# Sheet1.net
KiCad netlist of a schematic drawn in Altium Designer
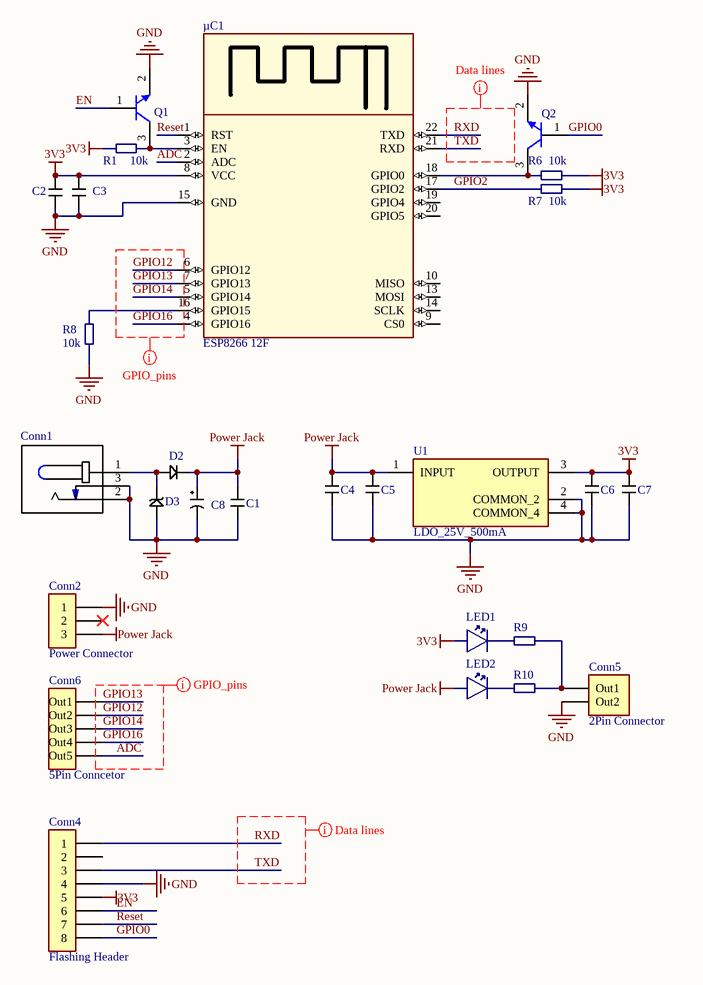
[diagram p0: Sheet1.SchDoc]

(export (version "E")
  (design (tool "Eeschema 10.0.6"))
  (components
    (comp (ref "C1") (value "Cap 0603") (footprint "CAP 0603") (libsource (lib "Schlib1") (part "Cap 0603")))
    (comp (ref "C2") (value "Cap 0603") (footprint "CAP 0603") (libsource (lib "Schlib1") (part "Cap 0603")))
    (comp (ref "C3") (value "Cap 0603") (footprint "CAP 0603") (libsource (lib "Schlib1") (part "Cap 0603")))
    (comp (ref "C4") (value "Cap 0603") (footprint "CAP 0603") (libsource (lib "Schlib1") (part "Cap 0603")))
    (comp (ref "C5") (value "Cap 0603") (footprint "CAP 0603") (libsource (lib "Schlib1") (part "Cap 0603")))
    (comp (ref "C6") (value "Cap 0603") (footprint "CAP 0603") (libsource (lib "Schlib1") (part "Cap 0603")))
    (comp (ref "C7") (value "Cap 0603") (footprint "CAP 0603") (libsource (lib "Schlib1") (part "Cap 0603")))
    (comp (ref "C8") (value "ElcoCap") (footprint "SMD Elco") (libsource (lib "Schlib1") (part "ElcoCap")))
    (comp (ref "Conn1")
      (value "Power Jack SMD rechtwinklig")
      (footprint "Power Jack")
      (libsource (lib "Schlib1") (part "Power Jack SMD rechtwinklig"))
    )
    (comp (ref "Conn2")
      (value "Power Connector")
      (footprint "3Pin CONNECTOR")
      (libsource (lib "Schlib1") (part "3Pin Connector"))
    )
    (comp (ref "Conn4")
      (value "Flashing Header")
      (footprint "Flashing header 2*5")
      (libsource (lib "Schlib1") (part "Flashing Header"))
    )
    (comp (ref "Conn5")
      (value "2Pin Connector")
      (footprint "2PIN Connector")
      (libsource (lib "Schlib1") (part "2Pin Connector"))
    )
    (comp (ref "Conn6")
      (value "5Pin Conncetor")
      (footprint "5PIN CONNECTOR")
      (libsource (lib "Schlib1") (part "5Pin Conncetor"))
    )
    (comp (ref "D2")
      (value "Schottky Diode")
      (footprint "SS34-HF")
      (libsource (lib "Schlib1") (part "Schottky Diode"))
    )
    (comp (ref "D3") (value "TVS Diode") (footprint "SMAJ24A") (libsource (lib "Schlib1") (part "TVS Diode")))
    (comp (ref "LED1") (value "LED SMD") (footprint "LED 0603") (libsource (lib "Schlib1") (part "LED SMD")))
    (comp (ref "LED2") (value "LED SMD") (footprint "LED 0603") (libsource (lib "Schlib1") (part "LED SMD")))
    (comp (ref "Q1")
      (value "BC818-40LT1G")
      (footprint "ONSC-SOT-23-3-318-08_V")
      (description "General Purpose Transistor, NPN Silicon, 3-Pin SOT-23, Pb-Free, Tape and Reel")
      (fields (field (name "MANUFACTURER") "On Semiconductor"))
      (libsource (lib "Altium Content Vault") (part "ONSC-NPN-B1E2C3-3"))
    )
    (comp (ref "Q2")
      (value "BC818-40LT1G")
      (footprint "ONSC-SOT-23-3-318-08_V")
      (description "General Purpose Transistor, NPN Silicon, 3-Pin SOT-23, Pb-Free, Tape and Reel")
      (fields (field (name "MANUFACTURER") "On Semiconductor"))
      (libsource (lib "Altium Content Vault") (part "ONSC-NPN-B1E2C3-3"))
    )
    (comp (ref "R1") (value "10k") (footprint "RES 0603") (libsource (lib "Schlib1") (part "Res 0603")))
    (comp (ref "R6") (value "10k") (footprint "RES 0603") (libsource (lib "Schlib1") (part "Res 0603")))
    (comp (ref "R7") (value "10k") (footprint "RES 0603") (libsource (lib "Schlib1") (part "Res 0603")))
    (comp (ref "R8") (value "10k") (footprint "RES 0603") (libsource (lib "Schlib1") (part "Res 0603")))
    (comp (ref "R9") (value "Res 0603") (footprint "RES 0603") (libsource (lib "Schlib1") (part "Res 0603")))
    (comp (ref "R10") (value "Res 0603") (footprint "RES 0603") (libsource (lib "Schlib1") (part "Res 0603")))
    (comp (ref "U1")
      (value "LDO_25V_500mA")
      (footprint "UA78M33CDCYRG3")
      (libsource (lib "Schlib1") (part "LDO_25V_500mA"))
    )
    (comp (ref "µC1")
      (value "ESP8266 12F")
      (footprint "ESP8266 12F")
      (libsource (lib "Schlib1") (part "ESP8266 12F"))
    )
  )
  (nets
    (net (code "1") (name "/ADC") (class "Default")
      (node (ref "Conn6") (pin "5") (pinfunction "Out5_5") (pintype "passive"))
      (node (ref "µC1") (pin "2") (pinfunction "ADC_2") (pintype "bidirectional"))
    )
    (net (code "2") (name "/EN") (class "Default")
      (node (ref "Conn4") (pin "6") (pinfunction "6_6") (pintype "passive"))
      (node (ref "Q1") (pin "1") (pinfunction "B_1") (pintype "passive"))
    )
    (net (code "3") (name "/GPIO0") (class "Default")
      (node (ref "Conn4") (pin "8") (pinfunction "8_8") (pintype "passive"))
      (node (ref "Q2") (pin "1") (pinfunction "B_1") (pintype "passive"))
    )
    (net (code "4") (name "/GPIO2") (class "Default")
      (node (ref "R7") (pin "1") (pinfunction "1_1") (pintype "passive"))
      (node (ref "µC1") (pin "17") (pinfunction "GPIO2_17") (pintype "bidirectional"))
    )
    (net (code "5") (name "/GPIO12") (class "Default")
      (node (ref "Conn6") (pin "2") (pinfunction "Out2_2") (pintype "passive"))
      (node (ref "µC1") (pin "6") (pinfunction "GPIO12_6") (pintype "bidirectional"))
    )
    (net (code "6") (name "/GPIO13") (class "Default")
      (node (ref "Conn6") (pin "1") (pinfunction "Out1_1") (pintype "passive"))
      (node (ref "µC1") (pin "7") (pinfunction "GPIO13_7") (pintype "bidirectional"))
    )
    (net (code "7") (name "/GPIO14") (class "Default")
      (node (ref "Conn6") (pin "3") (pinfunction "Out3_3") (pintype "passive"))
      (node (ref "µC1") (pin "5") (pinfunction "GPIO14_5") (pintype "bidirectional"))
    )
    (net (code "8") (name "/GPIO16") (class "Default")
      (node (ref "Conn6") (pin "4") (pinfunction "Out4_4") (pintype "passive"))
      (node (ref "µC1") (pin "4") (pinfunction "GPIO16_4") (pintype "bidirectional"))
    )
    (net (code "9") (name "/RXD") (class "Default")
      (node (ref "Conn4") (pin "1") (pinfunction "1_1") (pintype "passive"))
      (node (ref "µC1") (pin "22") (pinfunction "TXD_22") (pintype "bidirectional"))
    )
    (net (code "10") (name "/Reset") (class "Default")
      (node (ref "Conn4") (pin "7") (pinfunction "7_7") (pintype "passive"))
      (node (ref "µC1") (pin "1") (pinfunction "RST_1") (pintype "bidirectional"))
    )
    (net (code "11") (name "/TXD") (class "Default")
      (node (ref "Conn4") (pin "3") (pinfunction "3_3") (pintype "passive"))
      (node (ref "µC1") (pin "21") (pinfunction "RXD_21") (pintype "bidirectional"))
    )
    (net (code "12") (name "3V3") (class "Default")
      (node (ref "C2") (pin "2") (pinfunction "2_2") (pintype "passive"))
      (node (ref "C3") (pin "2") (pinfunction "2_2") (pintype "passive"))
      (node (ref "C6") (pin "2") (pinfunction "2_2") (pintype "passive"))
      (node (ref "C7") (pin "2") (pinfunction "2_2") (pintype "passive"))
      (node (ref "Conn4") (pin "5") (pinfunction "5_5") (pintype "passive"))
      (node (ref "LED1") (pin "1") (pinfunction "1_1") (pintype "passive"))
      (node (ref "R1") (pin "2") (pinfunction "2_2") (pintype "passive"))
      (node (ref "R6") (pin "2") (pinfunction "2_2") (pintype "passive"))
      (node (ref "R7") (pin "2") (pinfunction "2_2") (pintype "passive"))
      (node (ref "U1") (pin "3") (pinfunction "OUTPUT_3") (pintype "passive"))
      (node (ref "µC1") (pin "8") (pinfunction "VCC_8") (pintype "bidirectional"))
    )
    (net (code "13") (name "GND") (class "Default")
      (node (ref "C1") (pin "1") (pinfunction "1_1") (pintype "passive"))
      (node (ref "C2") (pin "1") (pinfunction "1_1") (pintype "passive"))
      (node (ref "C3") (pin "1") (pinfunction "1_1") (pintype "passive"))
      (node (ref "C4") (pin "1") (pinfunction "1_1") (pintype "passive"))
      (node (ref "C5") (pin "1") (pinfunction "1_1") (pintype "passive"))
      (node (ref "C6") (pin "1") (pinfunction "1_1") (pintype "passive"))
      (node (ref "C7") (pin "1") (pinfunction "1_1") (pintype "passive"))
      (node (ref "C8") (pin "2") (pinfunction "N_2") (pintype "passive"))
      (node (ref "Conn1") (pin "2") (pinfunction "2_2") (pintype "passive"))
      (node (ref "Conn1") (pin "3") (pinfunction "3_3") (pintype "passive"))
      (node (ref "Conn2") (pin "3") (pinfunction "1_3") (pintype "passive"))
      (node (ref "Conn4") (pin "4") (pinfunction "4_4") (pintype "passive"))
      (node (ref "Conn5") (pin "2") (pinfunction "Out2_2") (pintype "passive"))
      (node (ref "D3") (pin "1") (pinfunction "1_1") (pintype "passive"))
      (node (ref "Q1") (pin "2") (pinfunction "E_2") (pintype "passive"))
      (node (ref "Q2") (pin "2") (pinfunction "E_2") (pintype "passive"))
      (node (ref "R8") (pin "1") (pinfunction "1_1") (pintype "passive"))
      (node (ref "U1") (pin "2") (pinfunction "COMMON_2_2") (pintype "passive"))
      (node (ref "U1") (pin "4") (pinfunction "COMMON_4_4") (pintype "passive"))
      (node (ref "µC1") (pin "15") (pinfunction "GND_15") (pintype "bidirectional"))
    )
    (net (code "14") (name "Net-(Conn1-Pad1)") (class "Default")
      (node (ref "Conn1") (pin "1") (pinfunction "1_1") (pintype "passive"))
      (node (ref "D2") (pin "1") (pinfunction "1_1") (pintype "passive"))
      (node (ref "D3") (pin "2") (pinfunction "2_2") (pintype "passive"))
    )
    (net (code "15") (name "Net-(Conn5-Out1)") (class "Default")
      (node (ref "Conn5") (pin "1") (pinfunction "Out1_1") (pintype "passive"))
      (node (ref "R10") (pin "2") (pinfunction "2_2") (pintype "passive"))
      (node (ref "R9") (pin "2") (pinfunction "2_2") (pintype "passive"))
    )
    (net (code "16") (name "Net-(LED1-Pad2)") (class "Default")
      (node (ref "LED1") (pin "2") (pinfunction "2_2") (pintype "passive"))
      (node (ref "R9") (pin "1") (pinfunction "1_1") (pintype "passive"))
    )
    (net (code "17") (name "Net-(LED2-Pad2)") (class "Default")
      (node (ref "LED2") (pin "2") (pinfunction "2_2") (pintype "passive"))
      (node (ref "R10") (pin "1") (pinfunction "1_1") (pintype "passive"))
    )
    (net (code "18") (name "Net-(Q1-C)") (class "Default")
      (node (ref "Q1") (pin "3") (pinfunction "C_3") (pintype "passive"))
      (node (ref "R1") (pin "1") (pinfunction "1_1") (pintype "passive"))
      (node (ref "µC1") (pin "3") (pinfunction "EN_3") (pintype "bidirectional"))
    )
    (net (code "19") (name "Net-(Q2-C)") (class "Default")
      (node (ref "Q2") (pin "3") (pinfunction "C_3") (pintype "passive"))
      (node (ref "R6") (pin "1") (pinfunction "1_1") (pintype "passive"))
      (node (ref "µC1") (pin "18") (pinfunction "GPIO0_18") (pintype "bidirectional"))
    )
    (net (code "20") (name "Net-(µC1-GPIO15)") (class "Default")
      (node (ref "R8") (pin "2") (pinfunction "2_2") (pintype "passive"))
      (node (ref "µC1") (pin "16") (pinfunction "GPIO15_16") (pintype "bidirectional"))
    )
    (net (code "21") (name "Power Jack") (class "Default")
      (node (ref "C1") (pin "2") (pinfunction "2_2") (pintype "passive"))
      (node (ref "C4") (pin "2") (pinfunction "2_2") (pintype "passive"))
      (node (ref "C5") (pin "2") (pinfunction "2_2") (pintype "passive"))
      (node (ref "C8") (pin "1") (pinfunction "P_1") (pintype "passive"))
      (node (ref "Conn2") (pin "1") (pinfunction "3_1") (pintype "passive"))
      (node (ref "D2") (pin "2") (pinfunction "2_2") (pintype "passive"))
      (node (ref "LED2") (pin "1") (pinfunction "1_1") (pintype "passive"))
      (node (ref "U1") (pin "1") (pinfunction "INPUT_1") (pintype "passive"))
    )
    (net (code "22") (name "unconnected-(Conn2-Pad2)") (class "Default")
      (node (ref "Conn2") (pin "2") (pinfunction "2_2") (pintype "passive+no_connect"))
    )
    (net (code "23") (name "unconnected-(Conn4-Pad2)") (class "Default")
      (node (ref "Conn4") (pin "2") (pinfunction "2_2") (pintype "passive"))
    )
    (net (code "24") (name "unconnected-(µC1-CS0-Pad9)") (class "Default")
      (node (ref "µC1") (pin "9") (pinfunction "CS0_9") (pintype "bidirectional"))
    )
    (net (code "25") (name "unconnected-(µC1-GPIO4-Pad19)") (class "Default")
      (node (ref "µC1") (pin "19") (pinfunction "GPIO4_19") (pintype "bidirectional"))
    )
    (net (code "26") (name "unconnected-(µC1-GPIO5-Pad20)") (class "Default")
      (node (ref "µC1") (pin "20") (pinfunction "GPIO5_20") (pintype "bidirectional"))
    )
    (net (code "27") (name "unconnected-(µC1-MISO-Pad10)") (class "Default")
      (node (ref "µC1") (pin "10") (pinfunction "MISO_10") (pintype "bidirectional"))
    )
    (net (code "28") (name "unconnected-(µC1-MOSI-Pad13)") (class "Default")
      (node (ref "µC1") (pin "13") (pinfunction "MOSI_13") (pintype "bidirectional"))
    )
    (net (code "29") (name "unconnected-(µC1-SCLK-Pad14)") (class "Default")
      (node (ref "µC1") (pin "14") (pinfunction "SCLK_14") (pintype "bidirectional"))
    )
  )
)
